# KNLWiring.net
KiCad netlist of a schematic drawn in EAGLE
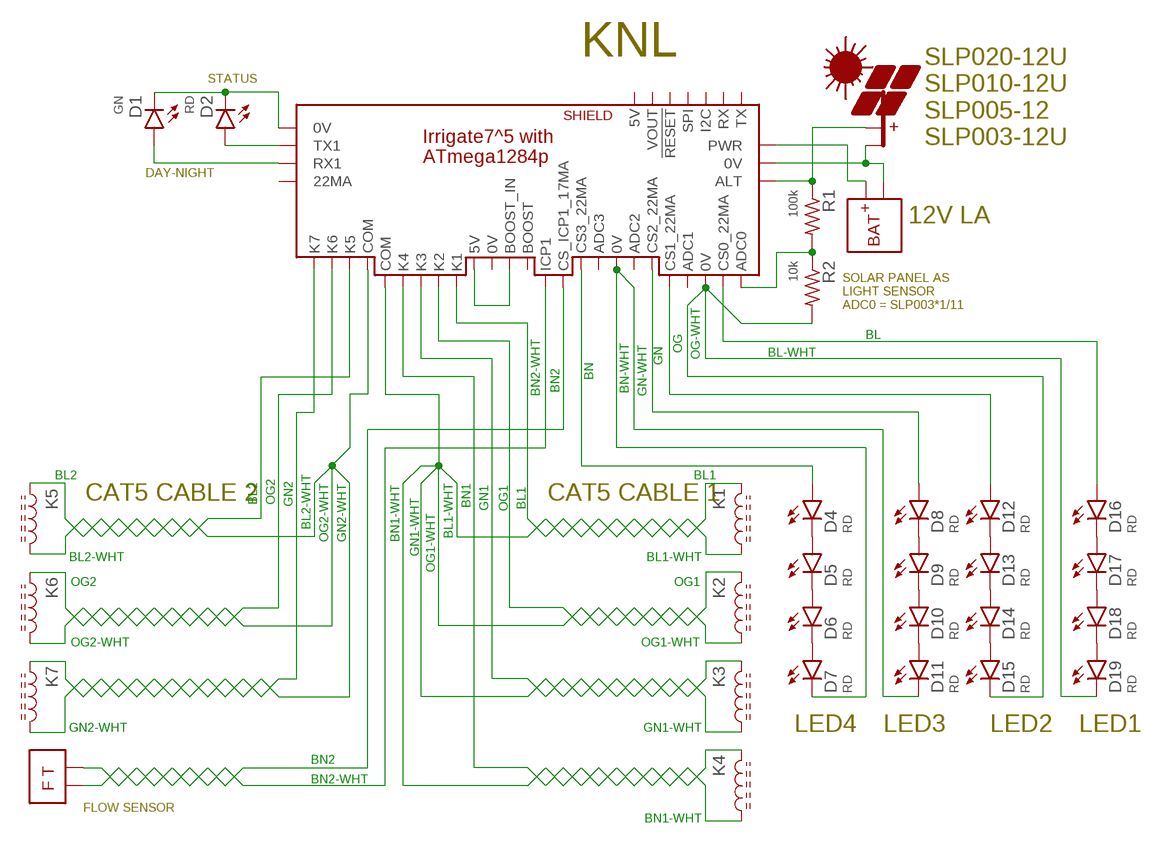
[diagram p0: schematic, sheet 1]

(export (version "E")
  (design (tool "Eeschema 10.0.6"))
  (components
    (comp (ref "D1")
      (value "GN")
      (footprint "eagle-import:LED5MM")
      (libsource (lib "eagle-import") (part "LED5MM"))
    )
    (comp (ref "D2")
      (value "RD")
      (footprint "eagle-import:LED5MM")
      (libsource (lib "eagle-import") (part "LED5MM"))
    )
    (comp (ref "D4")
      (value "RD")
      (footprint "eagle-import:LED5MM")
      (libsource (lib "eagle-import") (part "LED5MM"))
    )
    (comp (ref "D5")
      (value "RD")
      (footprint "eagle-import:LED5MM")
      (libsource (lib "eagle-import") (part "LED5MM"))
    )
    (comp (ref "D6")
      (value "RD")
      (footprint "eagle-import:LED5MM")
      (libsource (lib "eagle-import") (part "LED5MM"))
    )
    (comp (ref "D7")
      (value "RD")
      (footprint "eagle-import:LED5MM")
      (libsource (lib "eagle-import") (part "LED5MM"))
    )
    (comp (ref "D8")
      (value "RD")
      (footprint "eagle-import:LED5MM")
      (libsource (lib "eagle-import") (part "LED5MM"))
    )
    (comp (ref "D9")
      (value "RD")
      (footprint "eagle-import:LED5MM")
      (libsource (lib "eagle-import") (part "LED5MM"))
    )
    (comp (ref "D10")
      (value "RD")
      (footprint "eagle-import:LED5MM")
      (libsource (lib "eagle-import") (part "LED5MM"))
    )
    (comp (ref "D11")
      (value "RD")
      (footprint "eagle-import:LED5MM")
      (libsource (lib "eagle-import") (part "LED5MM"))
    )
    (comp (ref "D12")
      (value "RD")
      (footprint "eagle-import:LED5MM")
      (libsource (lib "eagle-import") (part "LED5MM"))
    )
    (comp (ref "D13")
      (value "RD")
      (footprint "eagle-import:LED5MM")
      (libsource (lib "eagle-import") (part "LED5MM"))
    )
    (comp (ref "D14")
      (value "RD")
      (footprint "eagle-import:LED5MM")
      (libsource (lib "eagle-import") (part "LED5MM"))
    )
    (comp (ref "D15")
      (value "RD")
      (footprint "eagle-import:LED5MM")
      (libsource (lib "eagle-import") (part "LED5MM"))
    )
    (comp (ref "D16")
      (value "RD")
      (footprint "eagle-import:LED5MM")
      (libsource (lib "eagle-import") (part "LED5MM"))
    )
    (comp (ref "D17")
      (value "RD")
      (footprint "eagle-import:LED5MM")
      (libsource (lib "eagle-import") (part "LED5MM"))
    )
    (comp (ref "D18")
      (value "RD")
      (footprint "eagle-import:LED5MM")
      (libsource (lib "eagle-import") (part "LED5MM"))
    )
    (comp (ref "D19")
      (value "RD")
      (footprint "eagle-import:LED5MM")
      (libsource (lib "eagle-import") (part "LED5MM"))
    )
    (comp (ref "K1")
      (value "L0805")
      (footprint "eagle-import:C0805(2012)")
      (libsource (lib "eagle-import") (part "L0805"))
    )
    (comp (ref "K2")
      (value "L0805")
      (footprint "eagle-import:C0805(2012)")
      (libsource (lib "eagle-import") (part "L0805"))
    )
    (comp (ref "K3")
      (value "L0805")
      (footprint "eagle-import:C0805(2012)")
      (libsource (lib "eagle-import") (part "L0805"))
    )
    (comp (ref "K4")
      (value "L0805")
      (footprint "eagle-import:C0805(2012)")
      (libsource (lib "eagle-import") (part "L0805"))
    )
    (comp (ref "K5")
      (value "L0805")
      (footprint "eagle-import:C0805(2012)")
      (libsource (lib "eagle-import") (part "L0805"))
    )
    (comp (ref "K6")
      (value "L0805")
      (footprint "eagle-import:C0805(2012)")
      (libsource (lib "eagle-import") (part "L0805"))
    )
    (comp (ref "K7")
      (value "L0805")
      (footprint "eagle-import:C0805(2012)")
      (libsource (lib "eagle-import") (part "L0805"))
    )
    (comp (ref "PV4")
      (value "PV")
      (footprint "eagle-import:NA-30")
      (libsource (lib "eagle-import") (part "PV"))
    )
    (comp (ref "R1")
      (value "100k")
      (footprint "eagle-import:C0805(2012)")
      (libsource (lib "eagle-import") (part "R0805"))
    )
    (comp (ref "R2")
      (value "10k")
      (footprint "eagle-import:C0805(2012)")
      (libsource (lib "eagle-import") (part "R0805"))
    )
    (comp (ref "U$1")
      (value "IRRIGATE7")
      (footprint "eagle-import:WITH_RPU_NAMES")
      (libsource (lib "eagle-import") (part "IRRIGATE7"))
    )
    (comp (ref "U$3")
      (value "FT")
      (footprint "eagle-import:NA-30")
      (libsource (lib "eagle-import") (part "FT"))
    )
    (comp (ref "U$7")
      (value "BAT")
      (footprint "eagle-import:NA-30")
      (libsource (lib "eagle-import") (part "BAT"))
    )
  )
  (nets
    (net (code "1") (name "/BL") (class "Default")
      (node (ref "D16") (pin "A") (pinfunction "A_A") (pintype "passive"))
      (node (ref "U$1") (pin "22MA@ADC0") (pinfunction "CS0_22MA_22MA@ADC0") (pintype "bidirectional"))
    )
    (net (code "2") (name "/BL-WHT") (class "Default")
      (node (ref "D19") (pin "K") (pinfunction "K_K") (pintype "passive"))
    )
    (net (code "3") (name "/BL1") (class "Default")
      (node (ref "K1") (pin "1") (pinfunction "1_1") (pintype "passive"))
      (node (ref "U$1") (pin "K1") (pinfunction "K1_K1") (pintype "bidirectional"))
    )
    (net (code "4") (name "/BL1-WHT") (class "Default")
      (node (ref "K1") (pin "2") (pinfunction "2_2") (pintype "passive"))
    )
    (net (code "5") (name "/BL2") (class "Default")
      (node (ref "K5") (pin "1") (pinfunction "1_1") (pintype "passive"))
      (node (ref "U$1") (pin "K5") (pinfunction "K5_K5") (pintype "bidirectional"))
    )
    (net (code "6") (name "/BL2-WHT") (class "Default")
      (node (ref "K5") (pin "2") (pinfunction "2_2") (pintype "passive"))
    )
    (net (code "7") (name "/BN") (class "Default")
      (node (ref "D4") (pin "A") (pinfunction "A_A") (pintype "passive"))
      (node (ref "U$1") (pin "22MA@ADC5") (pinfunction "CS3_22MA_22MA@ADC5") (pintype "bidirectional"))
    )
    (net (code "8") (name "/BN-WHT") (class "Default")
      (node (ref "D7") (pin "K") (pinfunction "K_K") (pintype "passive"))
    )
    (net (code "9") (name "/BN1") (class "Default")
      (node (ref "K4") (pin "1") (pinfunction "1_1") (pintype "passive"))
      (node (ref "U$1") (pin "K4") (pinfunction "K4_K4") (pintype "bidirectional"))
    )
    (net (code "10") (name "/BN1-WHT") (class "Default")
      (node (ref "K4") (pin "2") (pinfunction "2_2") (pintype "passive"))
    )
    (net (code "11") (name "/BN2") (class "Default")
      (node (ref "U$1") (pin "17MA@ICP1") (pinfunction "CS_ICP1_17MA_17MA@ICP1") (pintype "bidirectional"))
      (node (ref "U$3") (pin "2") (pinfunction "PWR_2") (pintype "bidirectional"))
    )
    (net (code "12") (name "/BN2-WHT") (class "Default")
      (node (ref "U$1") (pin "ICP1") (pinfunction "ICP1_ICP1") (pintype "bidirectional"))
      (node (ref "U$3") (pin "1") (pinfunction "PL_1") (pintype "bidirectional"))
    )
    (net (code "13") (name "/GN") (class "Default")
      (node (ref "D8") (pin "A") (pinfunction "A_A") (pintype "passive"))
      (node (ref "U$1") (pin "22MA@ADC4") (pinfunction "CS2_22MA_22MA@ADC4") (pintype "bidirectional"))
    )
    (net (code "14") (name "/GN-WHT") (class "Default")
      (node (ref "D11") (pin "K") (pinfunction "K_K") (pintype "passive"))
      (node (ref "U$1") (pin "ICP3") (pinfunction "0V_ICP3") (pintype "bidirectional"))
    )
    (net (code "15") (name "/GN1") (class "Default")
      (node (ref "K3") (pin "1") (pinfunction "1_1") (pintype "passive"))
      (node (ref "U$1") (pin "K3") (pinfunction "K3_K3") (pintype "bidirectional"))
    )
    (net (code "16") (name "/GN1-WHT") (class "Default")
      (node (ref "K3") (pin "2") (pinfunction "2_2") (pintype "passive"))
    )
    (net (code "17") (name "/GN2") (class "Default")
      (node (ref "K7") (pin "1") (pinfunction "1_1") (pintype "passive"))
      (node (ref "U$1") (pin "K7") (pinfunction "K7_K7") (pintype "bidirectional"))
    )
    (net (code "18") (name "/GN2-WHT") (class "Default")
      (node (ref "K7") (pin "2") (pinfunction "2_2") (pintype "passive"))
    )
    (net (code "19") (name "/OG") (class "Default")
      (node (ref "D12") (pin "A") (pinfunction "A_A") (pintype "passive"))
      (node (ref "U$1") (pin "22MA@ADC1") (pinfunction "CS1_22MA_22MA@ADC1") (pintype "bidirectional"))
    )
    (net (code "20") (name "/OG-WHT") (class "Default")
      (node (ref "D15") (pin "K") (pinfunction "K_K") (pintype "passive"))
      (node (ref "U$1") (pin "0V@ADC2") (pinfunction "0V_0V@ADC2") (pintype "bidirectional"))
    )
    (net (code "21") (name "/OG1") (class "Default")
      (node (ref "K2") (pin "1") (pinfunction "1_1") (pintype "passive"))
      (node (ref "U$1") (pin "K2") (pinfunction "K2_K2") (pintype "bidirectional"))
    )
    (net (code "22") (name "/OG1-WHT") (class "Default")
      (node (ref "K2") (pin "2") (pinfunction "2_2") (pintype "passive"))
    )
    (net (code "23") (name "/OG2") (class "Default")
      (node (ref "K6") (pin "1") (pinfunction "1_1") (pintype "passive"))
      (node (ref "U$1") (pin "K6") (pinfunction "K6_K6") (pintype "bidirectional"))
    )
    (net (code "24") (name "/OG2-WHT") (class "Default")
      (node (ref "K6") (pin "2") (pinfunction "2_2") (pintype "passive"))
    )
    (net (code "25") (name "Net-(D1-PadK)") (class "Default")
      (node (ref "D1") (pin "K") (pinfunction "K_K") (pintype "passive"))
      (node (ref "D2") (pin "K") (pinfunction "K_K") (pintype "passive"))
      (node (ref "U$1") (pin "17MA@ICP3") (pinfunction "0V_17MA@ICP3") (pintype "bidirectional"))
    )
    (net (code "26") (name "Net-(D4-PadK)") (class "Default")
      (node (ref "D4") (pin "K") (pinfunction "K_K") (pintype "passive"))
      (node (ref "D5") (pin "A") (pinfunction "A_A") (pintype "passive"))
    )
    (net (code "27") (name "Net-(D5-PadK)") (class "Default")
      (node (ref "D5") (pin "K") (pinfunction "K_K") (pintype "passive"))
      (node (ref "D6") (pin "A") (pinfunction "A_A") (pintype "passive"))
    )
    (net (code "28") (name "Net-(D6-PadK)") (class "Default")
      (node (ref "D6") (pin "K") (pinfunction "K_K") (pintype "passive"))
      (node (ref "D7") (pin "A") (pinfunction "A_A") (pintype "passive"))
    )
    (net (code "29") (name "Net-(D8-PadK)") (class "Default")
      (node (ref "D8") (pin "K") (pinfunction "K_K") (pintype "passive"))
      (node (ref "D9") (pin "A") (pinfunction "A_A") (pintype "passive"))
    )
    (net (code "30") (name "Net-(D10-PadA)") (class "Default")
      (node (ref "D10") (pin "A") (pinfunction "A_A") (pintype "passive"))
      (node (ref "D9") (pin "K") (pinfunction "K_K") (pintype "passive"))
    )
    (net (code "31") (name "Net-(D10-PadK)") (class "Default")
      (node (ref "D10") (pin "K") (pinfunction "K_K") (pintype "passive"))
      (node (ref "D11") (pin "A") (pinfunction "A_A") (pintype "passive"))
    )
    (net (code "32") (name "Net-(D12-PadK)") (class "Default")
      (node (ref "D12") (pin "K") (pinfunction "K_K") (pintype "passive"))
      (node (ref "D13") (pin "A") (pinfunction "A_A") (pintype "passive"))
    )
    (net (code "33") (name "Net-(D13-PadK)") (class "Default")
      (node (ref "D13") (pin "K") (pinfunction "K_K") (pintype "passive"))
      (node (ref "D14") (pin "A") (pinfunction "A_A") (pintype "passive"))
    )
    (net (code "34") (name "Net-(D14-PadK)") (class "Default")
      (node (ref "D14") (pin "K") (pinfunction "K_K") (pintype "passive"))
      (node (ref "D15") (pin "A") (pinfunction "A_A") (pintype "passive"))
    )
    (net (code "35") (name "Net-(D16-PadK)") (class "Default")
      (node (ref "D16") (pin "K") (pinfunction "K_K") (pintype "passive"))
      (node (ref "D17") (pin "A") (pinfunction "A_A") (pintype "passive"))
    )
    (net (code "36") (name "Net-(D17-PadK)") (class "Default")
      (node (ref "D17") (pin "K") (pinfunction "K_K") (pintype "passive"))
      (node (ref "D18") (pin "A") (pinfunction "A_A") (pintype "passive"))
    )
    (net (code "37") (name "Net-(D18-PadK)") (class "Default")
      (node (ref "D18") (pin "K") (pinfunction "K_K") (pintype "passive"))
      (node (ref "D19") (pin "A") (pinfunction "A_A") (pintype "passive"))
    )
    (net (code "38") (name "Net-(PV4-+PV)") (class "Default")
      (node (ref "PV4") (pin "1") (pinfunction "+PV_1") (pintype "bidirectional"))
      (node (ref "R1") (pin "1") (pinfunction "1_1") (pintype "passive"))
      (node (ref "U$1") (pin "AUX") (pinfunction "ALT_AUX") (pintype "bidirectional"))
    )
    (net (code "39") (name "Net-(PV4--PV)") (class "Default")
      (node (ref "PV4") (pin "2") (pinfunction "-PV_2") (pintype "bidirectional"))
      (node (ref "U$1") (pin "0V@PWR") (pinfunction "0V_0V@PWR") (pintype "bidirectional"))
      (node (ref "U$7") (pin "2") (pinfunction "-BAT_2") (pintype "bidirectional"))
    )
    (net (code "40") (name "Net-(R1-Pad2)") (class "Default")
      (node (ref "R1") (pin "2") (pinfunction "2_2") (pintype "passive"))
      (node (ref "R2") (pin "1") (pinfunction "1_1") (pintype "passive"))
      (node (ref "U$1") (pin "ADC0") (pinfunction "ADC0_ADC0") (pintype "bidirectional"))
    )
    (net (code "41") (name "Net-(U$1-Pad5V)") (class "Default")
      (node (ref "U$1") (pin "5V") (pinfunction "5V_5V") (pintype "bidirectional"))
      (node (ref "U$1") (pin "BOOST_IN") (pinfunction "BOOST_IN_BOOST_IN") (pintype "bidirectional"))
    )
    (net (code "42") (name "Net-(U$1-RX1)") (class "Default")
      (node (ref "D1") (pin "A") (pinfunction "A_A") (pintype "passive"))
      (node (ref "U$1") (pin "DIO2") (pinfunction "RX1_DIO2") (pintype "bidirectional"))
    )
    (net (code "43") (name "Net-(U$1-TX1)") (class "Default")
      (node (ref "D2") (pin "A") (pinfunction "A_A") (pintype "passive"))
      (node (ref "U$1") (pin "DIO3") (pinfunction "TX1_DIO3") (pintype "bidirectional"))
    )
    (net (code "44") (name "Net-(U$7-+BAT)") (class "Default")
      (node (ref "U$1") (pin "PWR") (pinfunction "PWR_PWR") (pintype "bidirectional"))
      (node (ref "U$7") (pin "1") (pinfunction "+BAT_1") (pintype "bidirectional"))
    )
    (net (code "45") (name "unconnected-(R2-Pad2)") (class "Default")
      (node (ref "R2") (pin "2") (pinfunction "2_2") (pintype "passive"))
    )
    (net (code "46") (name "unconnected-(U$1-5V-PadSHLD_5V)") (class "Default")
      (node (ref "U$1") (pin "SHLD_5V") (pinfunction "5V_SHLD_5V") (pintype "bidirectional"))
    )
    (net (code "47") (name "unconnected-(U$1-22MA-Pad22MA@DIO2)") (class "Default")
      (node (ref "U$1") (pin "22MA@DIO2") (pinfunction "22MA_22MA@DIO2") (pintype "bidirectional"))
    )
    (net (code "48") (name "unconnected-(U$1-ADC2-PadADC4)") (class "Default")
      (node (ref "U$1") (pin "ADC4") (pinfunction "ADC2_ADC4") (pintype "bidirectional"))
    )
    (net (code "49") (name "unconnected-(U$1-ADC3-PadADC5)") (class "Default")
      (node (ref "U$1") (pin "ADC5") (pinfunction "ADC3_ADC5") (pintype "bidirectional"))
    )
    (net (code "50") (name "unconnected-(U$1-COM-PadCOM@K4)") (class "Default")
      (node (ref "U$1") (pin "COM@K4") (pinfunction "COM_COM@K4") (pintype "bidirectional"))
    )
    (net (code "51") (name "unconnected-(U$1-COM-PadCOM@K5)") (class "Default")
      (node (ref "U$1") (pin "COM@K5") (pinfunction "COM_COM@K5") (pintype "bidirectional"))
    )
    (net (code "52") (name "unconnected-(U$1-Pad0V)") (class "Default")
      (node (ref "U$1") (pin "0V") (pinfunction "0V_0V") (pintype "bidirectional"))
    )
    (net (code "53") (name "unconnected-(U$1-PadADC1)") (class "Default")
      (node (ref "U$1") (pin "ADC1") (pinfunction "ADC1_ADC1") (pintype "bidirectional"))
    )
    (net (code "54") (name "unconnected-(U$1-PadBOOST)") (class "Default")
      (node (ref "U$1") (pin "BOOST") (pinfunction "BOOST_BOOST") (pintype "bidirectional"))
    )
    (net (code "55") (name "unconnected-(U$1-PadI2C)") (class "Default")
      (node (ref "U$1") (pin "I2C") (pinfunction "I2C_I2C") (pintype "bidirectional"))
    )
    (net (code "56") (name "unconnected-(U$1-PadRX)") (class "Default")
      (node (ref "U$1") (pin "RX") (pinfunction "RX_RX") (pintype "bidirectional"))
    )
    (net (code "57") (name "unconnected-(U$1-PadSPI)") (class "Default")
      (node (ref "U$1") (pin "SPI") (pinfunction "SPI_SPI") (pintype "bidirectional"))
    )
    (net (code "58") (name "unconnected-(U$1-PadTX)") (class "Default")
      (node (ref "U$1") (pin "TX") (pinfunction "TX_TX") (pintype "bidirectional"))
    )
    (net (code "59") (name "unconnected-(U$1-VOUT-PadSHLD_VOUT)") (class "Default")
      (node (ref "U$1") (pin "SHLD_VOUT") (pinfunction "VOUT_SHLD_VOUT") (pintype "bidirectional"))
    )
    (net (code "60") (name "unconnected-(U$1-~{RESET}-Pad!RESET)") (class "Default")
      (node (ref "U$1") (pin "!RESET") (pinfunction "~{RESET}_!RESET") (pintype "bidirectional"))
    )
  )
)
